# back.net
KiCad netlist of a schematic drawn in EAGLE
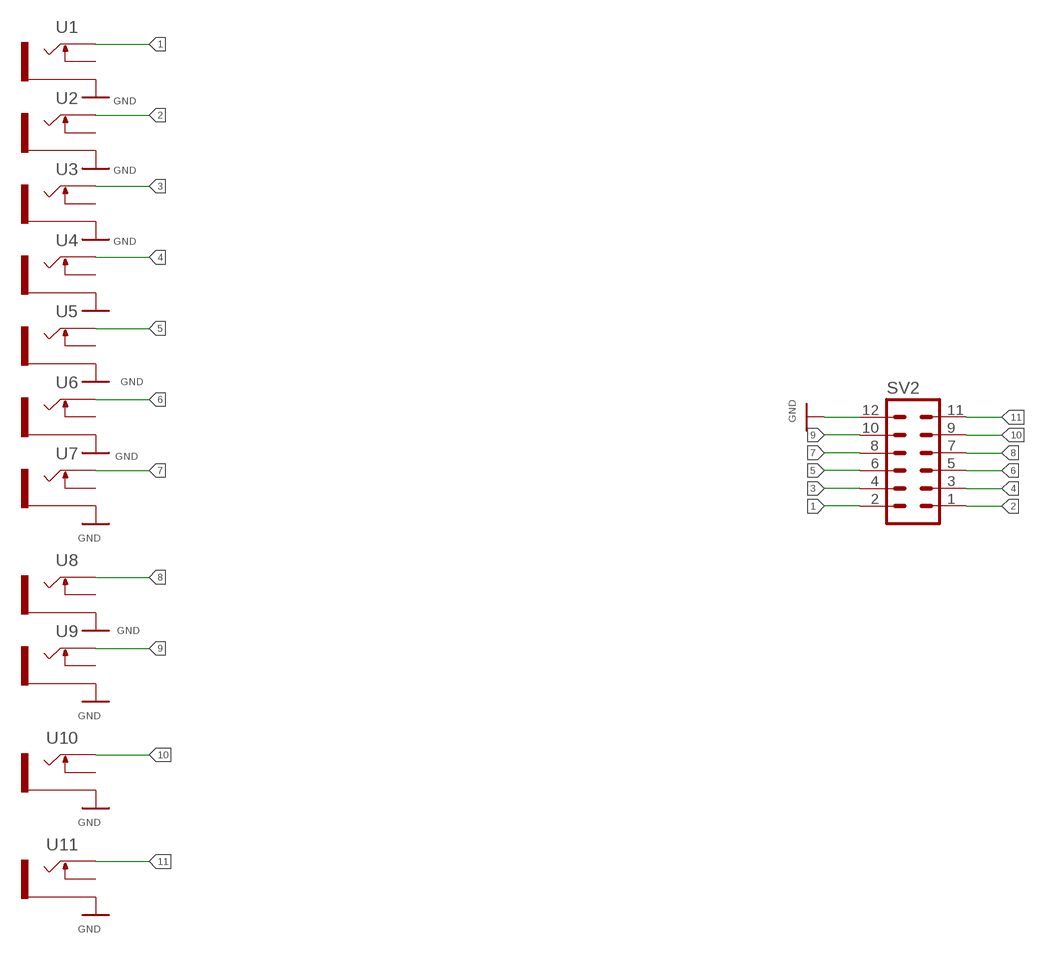
[diagram p0: schematic, sheet 1]

(export (version "E")
  (design (tool "Eeschema 10.0.6"))
  (components
    (comp (ref "SV2")
      (value "MA06-2")
      (footprint "eagle-import:MA06-2")
      (libsource (lib "eagle-import") (part "MA06-2"))
    )
    (comp (ref "U1")
      (value "THONKICONNNEW")
      (footprint "eagle-import:WQP-PJ301M-12_JACK")
      (libsource (lib "eagle-import") (part "THONKICONNNEW"))
    )
    (comp (ref "U2")
      (value "THONKICONN16PJ138")
      (footprint "eagle-import:WQP-PJ301M-12_JACK")
      (libsource (lib "eagle-import") (part "THONKICONN16PJ138"))
    )
    (comp (ref "U3")
      (value "THONKICONNNEW")
      (footprint "eagle-import:WQP-PJ301M-12_JACK")
      (libsource (lib "eagle-import") (part "THONKICONNNEW"))
    )
    (comp (ref "U4")
      (value "THONKICONNNEW")
      (footprint "eagle-import:WQP-PJ301M-12_JACK")
      (libsource (lib "eagle-import") (part "THONKICONNNEW"))
    )
    (comp (ref "U5")
      (value "THONKICONNNEW")
      (footprint "eagle-import:WQP-PJ301M-12_JACK")
      (libsource (lib "eagle-import") (part "THONKICONNNEW"))
    )
    (comp (ref "U6")
      (value "THONKICONNNEW")
      (footprint "eagle-import:WQP-PJ301M-12_JACK")
      (libsource (lib "eagle-import") (part "THONKICONNNEW"))
    )
    (comp (ref "U7")
      (value "THONKICONNNEW")
      (footprint "eagle-import:WQP-PJ301M-12_JACK")
      (libsource (lib "eagle-import") (part "THONKICONNNEW"))
    )
    (comp (ref "U8")
      (value "THONKICONNNEW")
      (footprint "eagle-import:WQP-PJ301M-12_JACK")
      (libsource (lib "eagle-import") (part "THONKICONNNEW"))
    )
    (comp (ref "U9")
      (value "THONKICONNNEW")
      (footprint "eagle-import:WQP-PJ301M-12_JACK")
      (libsource (lib "eagle-import") (part "THONKICONNNEW"))
    )
    (comp (ref "U10")
      (value "THONKICONNNEW")
      (footprint "eagle-import:WQP-PJ301M-12_JACK")
      (libsource (lib "eagle-import") (part "THONKICONNNEW"))
    )
    (comp (ref "U11")
      (value "THONKICONNNEW")
      (footprint "eagle-import:WQP-PJ301M-12_JACK")
      (libsource (lib "eagle-import") (part "THONKICONNNEW"))
    )
  )
  (nets
    (net (code "1") (name "1") (class "Default")
      (node (ref "SV2") (pin "2") (pinfunction "2_2") (pintype "passive"))
      (node (ref "U1") (pin "P$1_TIP") (pinfunction "TIP_P$1_TIP") (pintype "passive"))
    )
    (net (code "2") (name "2") (class "Default")
      (node (ref "SV2") (pin "1") (pinfunction "1_1") (pintype "passive"))
      (node (ref "U2") (pin "P$1_TIP") (pinfunction "TIP_P$1_TIP") (pintype "passive"))
    )
    (net (code "3") (name "3") (class "Default")
      (node (ref "SV2") (pin "4") (pinfunction "4_4") (pintype "passive"))
      (node (ref "U3") (pin "P$1_TIP") (pinfunction "TIP_P$1_TIP") (pintype "passive"))
    )
    (net (code "4") (name "4") (class "Default")
      (node (ref "SV2") (pin "3") (pinfunction "3_3") (pintype "passive"))
      (node (ref "U4") (pin "P$1_TIP") (pinfunction "TIP_P$1_TIP") (pintype "passive"))
    )
    (net (code "5") (name "5") (class "Default")
      (node (ref "SV2") (pin "6") (pinfunction "6_6") (pintype "passive"))
      (node (ref "U5") (pin "P$1_TIP") (pinfunction "TIP_P$1_TIP") (pintype "passive"))
    )
    (net (code "6") (name "6") (class "Default")
      (node (ref "SV2") (pin "5") (pinfunction "5_5") (pintype "passive"))
      (node (ref "U6") (pin "P$1_TIP") (pinfunction "TIP_P$1_TIP") (pintype "passive"))
    )
    (net (code "7") (name "7") (class "Default")
      (node (ref "SV2") (pin "8") (pinfunction "8_8") (pintype "passive"))
      (node (ref "U7") (pin "P$1_TIP") (pinfunction "TIP_P$1_TIP") (pintype "passive"))
    )
    (net (code "8") (name "8") (class "Default")
      (node (ref "SV2") (pin "7") (pinfunction "7_7") (pintype "passive"))
      (node (ref "U8") (pin "P$1_TIP") (pinfunction "TIP_P$1_TIP") (pintype "passive"))
    )
    (net (code "9") (name "9") (class "Default")
      (node (ref "SV2") (pin "10") (pinfunction "10_10") (pintype "passive"))
      (node (ref "U9") (pin "P$1_TIP") (pinfunction "TIP_P$1_TIP") (pintype "passive"))
    )
    (net (code "10") (name "10") (class "Default")
      (node (ref "SV2") (pin "9") (pinfunction "9_9") (pintype "passive"))
      (node (ref "U10") (pin "P$1_TIP") (pinfunction "TIP_P$1_TIP") (pintype "passive"))
    )
    (net (code "11") (name "11") (class "Default")
      (node (ref "SV2") (pin "11") (pinfunction "11_11") (pintype "passive"))
      (node (ref "U11") (pin "P$1_TIP") (pinfunction "TIP_P$1_TIP") (pintype "passive"))
    )
    (net (code "12") (name "GND") (class "Default")
      (node (ref "SV2") (pin "12") (pinfunction "12_12") (pintype "passive"))
      (node (ref "U1") (pin "P$3_SLEEVE") (pinfunction "SLEEVE_P$3_SLEEVE") (pintype "passive"))
      (node (ref "U10") (pin "P$3_SLEEVE") (pinfunction "SLEEVE_P$3_SLEEVE") (pintype "passive"))
      (node (ref "U11") (pin "P$3_SLEEVE") (pinfunction "SLEEVE_P$3_SLEEVE") (pintype "passive"))
      (node (ref "U2") (pin "P$3_SLEEVE") (pinfunction "SLEEVE_P$3_SLEEVE") (pintype "passive"))
      (node (ref "U3") (pin "P$3_SLEEVE") (pinfunction "SLEEVE_P$3_SLEEVE") (pintype "passive"))
      (node (ref "U4") (pin "P$3_SLEEVE") (pinfunction "SLEEVE_P$3_SLEEVE") (pintype "passive"))
      (node (ref "U5") (pin "P$3_SLEEVE") (pinfunction "SLEEVE_P$3_SLEEVE") (pintype "passive"))
      (node (ref "U6") (pin "P$3_SLEEVE") (pinfunction "SLEEVE_P$3_SLEEVE") (pintype "passive"))
      (node (ref "U7") (pin "P$3_SLEEVE") (pinfunction "SLEEVE_P$3_SLEEVE") (pintype "passive"))
      (node (ref "U8") (pin "P$3_SLEEVE") (pinfunction "SLEEVE_P$3_SLEEVE") (pintype "passive"))
      (node (ref "U9") (pin "P$3_SLEEVE") (pinfunction "SLEEVE_P$3_SLEEVE") (pintype "passive"))
    )
    (net (code "13") (name "unconnected-(U1-SWITCH-PadP$2_SWITCH)") (class "Default")
      (node (ref "U1") (pin "P$2_SWITCH") (pinfunction "SWITCH_P$2_SWITCH") (pintype "passive"))
    )
    (net (code "14") (name "unconnected-(U2-SWITCH-PadP$2_SWITCH)") (class "Default")
      (node (ref "U2") (pin "P$2_SWITCH") (pinfunction "SWITCH_P$2_SWITCH") (pintype "passive"))
    )
    (net (code "15") (name "unconnected-(U3-SWITCH-PadP$2_SWITCH)") (class "Default")
      (node (ref "U3") (pin "P$2_SWITCH") (pinfunction "SWITCH_P$2_SWITCH") (pintype "passive"))
    )
    (net (code "16") (name "unconnected-(U4-SWITCH-PadP$2_SWITCH)") (class "Default")
      (node (ref "U4") (pin "P$2_SWITCH") (pinfunction "SWITCH_P$2_SWITCH") (pintype "passive"))
    )
    (net (code "17") (name "unconnected-(U5-SWITCH-PadP$2_SWITCH)") (class "Default")
      (node (ref "U5") (pin "P$2_SWITCH") (pinfunction "SWITCH_P$2_SWITCH") (pintype "passive"))
    )
    (net (code "18") (name "unconnected-(U6-SWITCH-PadP$2_SWITCH)") (class "Default")
      (node (ref "U6") (pin "P$2_SWITCH") (pinfunction "SWITCH_P$2_SWITCH") (pintype "passive"))
    )
    (net (code "19") (name "unconnected-(U7-SWITCH-PadP$2_SWITCH)") (class "Default")
      (node (ref "U7") (pin "P$2_SWITCH") (pinfunction "SWITCH_P$2_SWITCH") (pintype "passive"))
    )
    (net (code "20") (name "unconnected-(U8-SWITCH-PadP$2_SWITCH)") (class "Default")
      (node (ref "U8") (pin "P$2_SWITCH") (pinfunction "SWITCH_P$2_SWITCH") (pintype "passive"))
    )
    (net (code "21") (name "unconnected-(U9-SWITCH-PadP$2_SWITCH)") (class "Default")
      (node (ref "U9") (pin "P$2_SWITCH") (pinfunction "SWITCH_P$2_SWITCH") (pintype "passive"))
    )
    (net (code "22") (name "unconnected-(U10-SWITCH-PadP$2_SWITCH)") (class "Default")
      (node (ref "U10") (pin "P$2_SWITCH") (pinfunction "SWITCH_P$2_SWITCH") (pintype "passive"))
    )
    (net (code "23") (name "unconnected-(U11-SWITCH-PadP$2_SWITCH)") (class "Default")
      (node (ref "U11") (pin "P$2_SWITCH") (pinfunction "SWITCH_P$2_SWITCH") (pintype "passive"))
    )
  )
)
